# phi-headphone-amp-opa2134.net
KiCad netlist of a schematic drawn in EAGLE
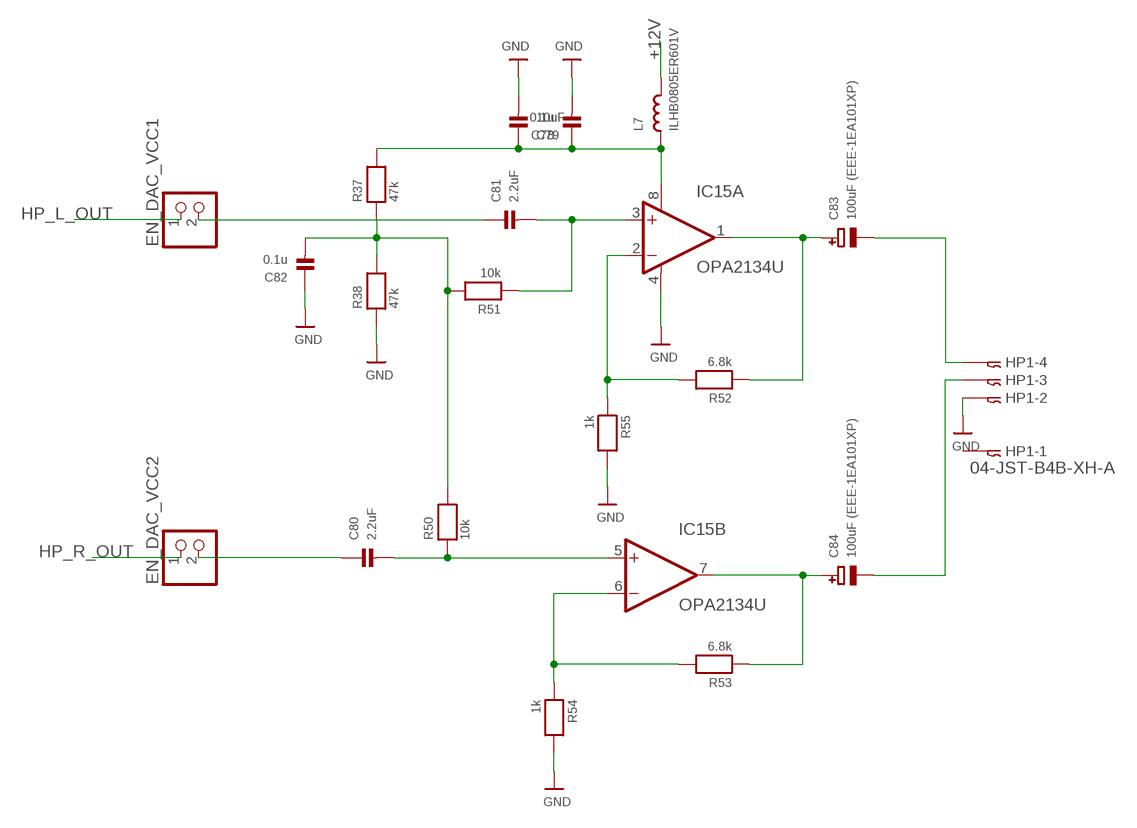
[diagram p0: schematic, sheet 1]

(export (version "E")
  (design (tool "Eeschema 10.0.6"))
  (components
    (comp (ref "C78")
      (value "0.1u")
      (footprint "eagle-import:0603")
      (libsource (lib "eagle-import") (part "CAP_CERAMIC0603"))
    )
    (comp (ref "C79")
      (value "10uF")
      (footprint "eagle-import:1206")
      (libsource (lib "eagle-import") (part "CAP_CERAMIC1206"))
    )
    (comp (ref "C80")
      (value "2.2uF")
      (footprint "eagle-import:_0805")
      (libsource (lib "eagle-import") (part "CAP_CERAMIC_0805"))
    )
    (comp (ref "C81")
      (value "2.2uF")
      (footprint "eagle-import:_0805")
      (libsource (lib "eagle-import") (part "CAP_CERAMIC_0805"))
    )
    (comp (ref "C82")
      (value "0.1u")
      (footprint "eagle-import:0603")
      (libsource (lib "eagle-import") (part "CAP_CERAMIC0603"))
    )
    (comp (ref "C83")
      (value "100uF (EEE-1EA101XP)")
      (footprint "eagle-import:PANASONIC_D")
      (libsource (lib "eagle-import") (part "CAP_ELECTROLYTICPANASONIC_D"))
    )
    (comp (ref "C84")
      (value "100uF (EEE-1EA101XP)")
      (footprint "eagle-import:PANASONIC_D")
      (libsource (lib "eagle-import") (part "CAP_ELECTROLYTICPANASONIC_D"))
    )
    (comp (ref "EN_DAC_VCC1")
      (value "HEADER-1X2")
      (footprint "eagle-import:1X02_OVAL")
      (libsource (lib "eagle-import") (part "HEADER-1X2"))
    )
    (comp (ref "EN_DAC_VCC2")
      (value "HEADER-1X2")
      (footprint "eagle-import:1X02_OVAL")
      (libsource (lib "eagle-import") (part "HEADER-1X2"))
    )
    (comp (ref "HP1")
      (value "04-JST-B4B-XH-A")
      (footprint "eagle-import:B4B-XH")
      (fields (field (name "MPN") "B4B-XH-A(LF)(SN)"))
      (libsource (lib "eagle-import") (part "04-JST-B4B-XH-A"))
    )
    (comp (ref "IC15")
      (value "OPA2134U")
      (footprint "eagle-import:SO08")
      (fields (field (name "MF") "TEXAS INSTRUMENTS") (field (name "MPN") "OPA2134UA"))
      (libsource (lib "eagle-import") (part "OPA2134U"))
    )
    (comp (ref "L7")
      (value "ILHB0805ER601V")
      (footprint "eagle-import:_0805")
      (libsource (lib "eagle-import") (part "INDUCTOR_0805"))
    )
    (comp (ref "R37")
      (value "47k")
      (footprint "eagle-import:_0805")
      (libsource (lib "eagle-import") (part "RESISTOR_0805"))
    )
    (comp (ref "R38")
      (value "47k")
      (footprint "eagle-import:_0805")
      (libsource (lib "eagle-import") (part "RESISTOR_0805"))
    )
    (comp (ref "R50")
      (value "10k")
      (footprint "eagle-import:_0805")
      (libsource (lib "eagle-import") (part "RESISTOR_0805"))
    )
    (comp (ref "R51")
      (value "10k")
      (footprint "eagle-import:_0805")
      (libsource (lib "eagle-import") (part "RESISTOR_0805"))
    )
    (comp (ref "R52")
      (value "6.8k")
      (footprint "eagle-import:_0805")
      (libsource (lib "eagle-import") (part "RESISTOR_0805"))
    )
    (comp (ref "R53")
      (value "6.8k")
      (footprint "eagle-import:_0805")
      (libsource (lib "eagle-import") (part "RESISTOR_0805"))
    )
    (comp (ref "R54")
      (value "1k")
      (footprint "eagle-import:_0805")
      (libsource (lib "eagle-import") (part "RESISTOR_0805"))
    )
    (comp (ref "R55")
      (value "1k")
      (footprint "eagle-import:_0805")
      (libsource (lib "eagle-import") (part "RESISTOR_0805"))
    )
  )
  (nets
    (net (code "1") (name "/+12V") (class "Default")
      (node (ref "L7") (pin "2") (pinfunction "2_2") (pintype "passive"))
    )
    (net (code "2") (name "/HP_L_OUT") (class "Default")
      (node (ref "EN_DAC_VCC1") (pin "1") (pinfunction "1_1") (pintype "passive"))
    )
    (net (code "3") (name "/HP_R_OUT") (class "Default")
      (node (ref "EN_DAC_VCC2") (pin "1") (pinfunction "1_1") (pintype "passive"))
    )
    (net (code "4") (name "GND") (class "Default")
      (node (ref "C78") (pin "2") (pinfunction "P$2_2") (pintype "passive"))
      (node (ref "C79") (pin "2") (pinfunction "P$2_2") (pintype "passive"))
      (node (ref "C82") (pin "1") (pinfunction "P$1_1") (pintype "passive"))
      (node (ref "HP1") (pin "P$2") (pinfunction "1_P$2") (pintype "passive"))
      (node (ref "IC15") (pin "4") (pinfunction "V-_4") (pintype "power_in"))
      (node (ref "R38") (pin "1") (pinfunction "1_1") (pintype "passive"))
      (node (ref "R54") (pin "2") (pinfunction "2_2") (pintype "passive"))
      (node (ref "R55") (pin "2") (pinfunction "2_2") (pintype "passive"))
    )
    (net (code "5") (name "Net-(C78-P$1)") (class "Default")
      (node (ref "C78") (pin "1") (pinfunction "P$1_1") (pintype "passive"))
      (node (ref "C79") (pin "1") (pinfunction "P$1_1") (pintype "passive"))
      (node (ref "IC15") (pin "8") (pinfunction "V+_8") (pintype "power_in"))
      (node (ref "L7") (pin "1") (pinfunction "1_1") (pintype "passive"))
      (node (ref "R37") (pin "2") (pinfunction "2_2") (pintype "passive"))
    )
    (net (code "6") (name "Net-(C80-P$1)") (class "Default")
      (node (ref "C80") (pin "1") (pinfunction "P$1_1") (pintype "passive"))
      (node (ref "EN_DAC_VCC2") (pin "2") (pinfunction "2_2") (pintype "passive"))
    )
    (net (code "7") (name "Net-(C80-P$2)") (class "Default")
      (node (ref "C80") (pin "2") (pinfunction "P$2_2") (pintype "passive"))
      (node (ref "IC15") (pin "5") (pinfunction "+IN_5") (pintype "input"))
      (node (ref "R50") (pin "1") (pinfunction "1_1") (pintype "passive"))
    )
    (net (code "8") (name "Net-(C81-P$1)") (class "Default")
      (node (ref "C81") (pin "1") (pinfunction "P$1_1") (pintype "passive"))
      (node (ref "EN_DAC_VCC1") (pin "2") (pinfunction "2_2") (pintype "passive"))
    )
    (net (code "9") (name "Net-(C81-P$2)") (class "Default")
      (node (ref "C81") (pin "2") (pinfunction "P$2_2") (pintype "passive"))
      (node (ref "IC15") (pin "3") (pinfunction "+IN_3") (pintype "input"))
      (node (ref "R51") (pin "1") (pinfunction "1_1") (pintype "passive"))
    )
    (net (code "10") (name "Net-(C82-P$2)") (class "Default")
      (node (ref "C82") (pin "2") (pinfunction "P$2_2") (pintype "passive"))
      (node (ref "R37") (pin "1") (pinfunction "1_1") (pintype "passive"))
      (node (ref "R38") (pin "2") (pinfunction "2_2") (pintype "passive"))
      (node (ref "R50") (pin "2") (pinfunction "2_2") (pintype "passive"))
      (node (ref "R51") (pin "2") (pinfunction "2_2") (pintype "passive"))
    )
    (net (code "11") (name "Net-(HP1C-1)") (class "Default")
      (node (ref "C84") (pin "-") (pinfunction "-_-") (pintype "passive"))
      (node (ref "HP1") (pin "P$3") (pinfunction "1_P$3") (pintype "passive"))
    )
    (net (code "12") (name "Net-(HP1D-1)") (class "Default")
      (node (ref "C83") (pin "-") (pinfunction "-_-") (pintype "passive"))
      (node (ref "HP1") (pin "P$4") (pinfunction "1_P$4") (pintype "passive"))
    )
    (net (code "13") (name "Net-(IC15A--IN)") (class "Default")
      (node (ref "IC15") (pin "2") (pinfunction "-IN_2") (pintype "input"))
      (node (ref "R52") (pin "2") (pinfunction "2_2") (pintype "passive"))
      (node (ref "R55") (pin "1") (pinfunction "1_1") (pintype "passive"))
    )
    (net (code "14") (name "Net-(IC15A-OUT)") (class "Default")
      (node (ref "C83") (pin "+") (pinfunction "+_+") (pintype "passive"))
      (node (ref "IC15") (pin "1") (pinfunction "OUT_1") (pintype "output"))
      (node (ref "R52") (pin "1") (pinfunction "1_1") (pintype "passive"))
    )
    (net (code "15") (name "Net-(IC15B--IN)") (class "Default")
      (node (ref "IC15") (pin "6") (pinfunction "-IN_6") (pintype "input"))
      (node (ref "R53") (pin "2") (pinfunction "2_2") (pintype "passive"))
      (node (ref "R54") (pin "1") (pinfunction "1_1") (pintype "passive"))
    )
    (net (code "16") (name "Net-(IC15B-OUT)") (class "Default")
      (node (ref "C84") (pin "+") (pinfunction "+_+") (pintype "passive"))
      (node (ref "IC15") (pin "7") (pinfunction "OUT_7") (pintype "output"))
      (node (ref "R53") (pin "1") (pinfunction "1_1") (pintype "passive"))
    )
    (net (code "17") (name "unconnected-(HP1A-1-PadP$1)") (class "Default")
      (node (ref "HP1") (pin "P$1") (pinfunction "1_P$1") (pintype "passive"))
    )
  )
)
